# datalogger1_1.net
KiCad netlist of a schematic drawn in EAGLE
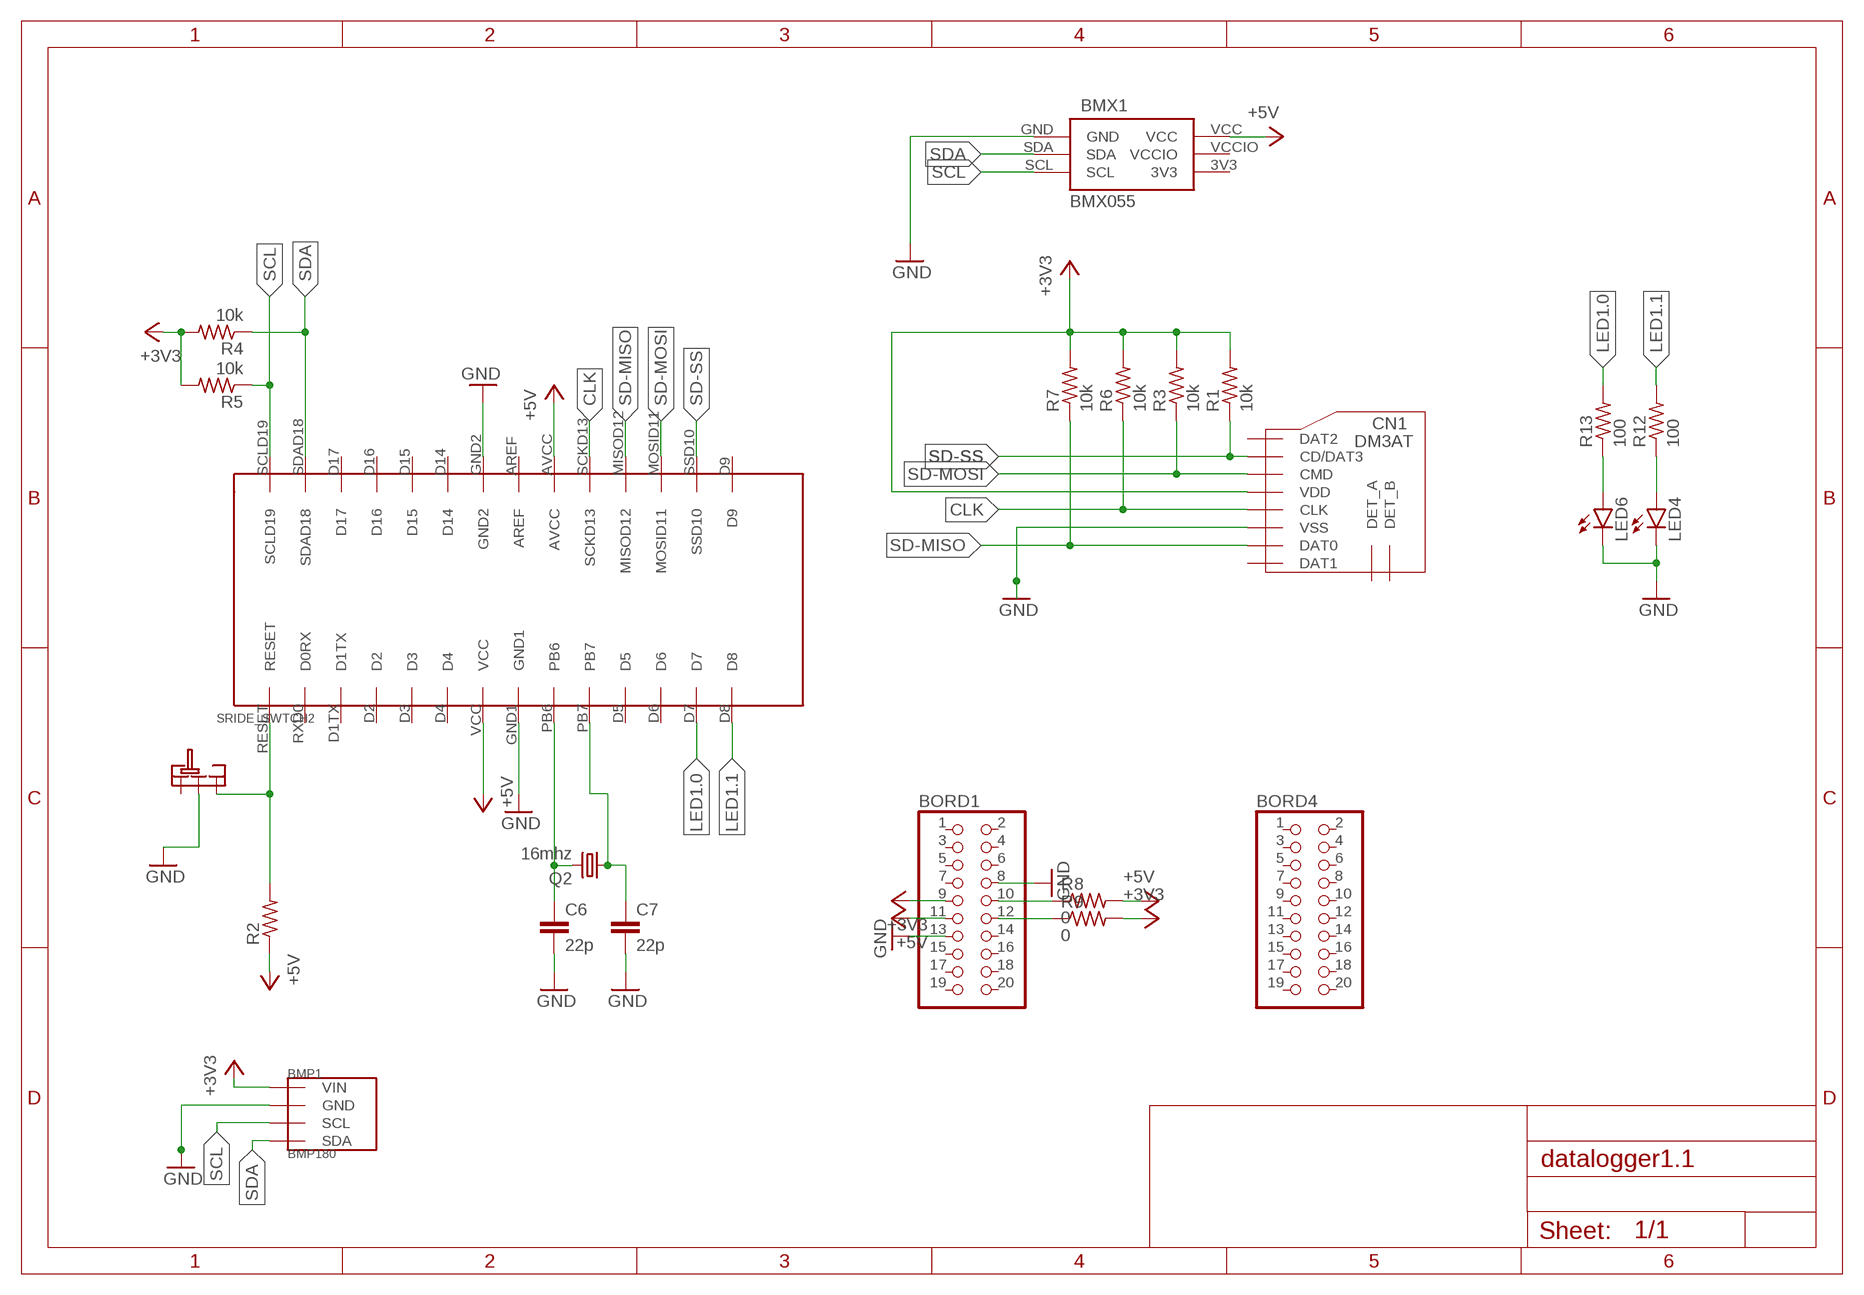
[diagram p0: schematic, sheet 1]

(export (version "E")
  (design (tool "Eeschema 10.0.6"))
  (components
    (comp (ref "BMP1")
      (value "BMP180")
      (footprint "eagle-import:GY-68")
      (libsource (lib "eagle-import") (part "BMP180"))
    )
    (comp (ref "BMX1")
      (value "BMX055")
      (footprint "eagle-import:BMX055")
      (libsource (lib "eagle-import") (part "BMX055"))
    )
    (comp (ref "BORD1")
      (value "PINHD-2X10/90")
      (footprint "eagle-import:2X10_90")
      (libsource (lib "eagle-import") (part "PINHD-2X10/90"))
    )
    (comp (ref "BORD4")
      (value "PINHD-2X10/90")
      (footprint "eagle-import:2X10_90")
      (libsource (lib "eagle-import") (part "PINHD-2X10/90"))
    )
    (comp (ref "C6")
      (value "22p")
      (footprint "eagle-import:C025-024X044")
      (libsource (lib "eagle-import") (part "C-EU025-024X044"))
    )
    (comp (ref "C7")
      (value "22p")
      (footprint "eagle-import:C025-024X044")
      (libsource (lib "eagle-import") (part "C-EU025-024X044"))
    )
    (comp (ref "CN1")
      (value "DM3AT")
      (footprint "eagle-import:DM3AT")
      (libsource (lib "eagle-import") (part "DM3AT"))
    )
    (comp (ref "LED4")
      (value "LED5MM")
      (footprint "eagle-import:LED5MM")
      (libsource (lib "eagle-import") (part "LED5MM"))
    )
    (comp (ref "LED6")
      (value "LED5MM")
      (footprint "eagle-import:LED5MM")
      (libsource (lib "eagle-import") (part "LED5MM"))
    )
    (comp (ref "Q2")
      (value "16mhz")
      (footprint "eagle-import:HC49_S")
      (libsource (lib "eagle-import") (part "CRYSTALHC49S"))
    )
    (comp (ref "R1")
      (value "10k")
      (footprint "eagle-import:0204_7")
      (libsource (lib "eagle-import") (part "R-US_0204/7"))
    )
    (comp (ref "R2")
      (value "R-US_0204/7")
      (footprint "eagle-import:0204_7")
      (libsource (lib "eagle-import") (part "R-US_0204/7"))
    )
    (comp (ref "R3")
      (value "10k")
      (footprint "eagle-import:0204_7")
      (libsource (lib "eagle-import") (part "R-US_0204/7"))
    )
    (comp (ref "R4")
      (value "10k")
      (footprint "eagle-import:0204_7")
      (libsource (lib "eagle-import") (part "R-US_0204/7"))
    )
    (comp (ref "R5")
      (value "10k")
      (footprint "eagle-import:0204_7")
      (libsource (lib "eagle-import") (part "R-US_0204/7"))
    )
    (comp (ref "R6")
      (value "10k")
      (footprint "eagle-import:0204_7")
      (libsource (lib "eagle-import") (part "R-US_0204/7"))
    )
    (comp (ref "R7")
      (value "10k")
      (footprint "eagle-import:0204_7")
      (libsource (lib "eagle-import") (part "R-US_0204/7"))
    )
    (comp (ref "R8")
      (value "0")
      (footprint "eagle-import:0204_7")
      (libsource (lib "eagle-import") (part "R-US_0204/7"))
    )
    (comp (ref "R9")
      (value "0")
      (footprint "eagle-import:0204_7")
      (libsource (lib "eagle-import") (part "R-US_0204/7"))
    )
    (comp (ref "R12")
      (value "100")
      (footprint "eagle-import:0204_7")
      (libsource (lib "eagle-import") (part "R-US_0204/7"))
    )
    (comp (ref "R13")
      (value "100")
      (footprint "eagle-import:0204_7")
      (libsource (lib "eagle-import") (part "R-US_0204/7"))
    )
    (comp (ref "SRIDE_SWTCH2")
      (value "SRIDE_SWITCH")
      (footprint "eagle-import:SRIDE_SWITCH")
      (libsource (lib "eagle-import") (part "SRIDE_SWITCH"))
    )
    (comp (ref "U$6")
      (value "ATMEGA238P")
      (footprint "eagle-import:ATMEGA328P")
      (libsource (lib "eagle-import") (part "ATMEGA238P"))
    )
  )
  (nets
    (net (code "1") (name "+3V3") (class "Default")
      (node (ref "BMP1") (pin "P1") (pinfunction "VIN_P1") (pintype "bidirectional"))
      (node (ref "BORD1") (pin "9") (pinfunction "9_9") (pintype "passive"))
      (node (ref "CN1") (pin "VDD") (pinfunction "VDD_VDD") (pintype "bidirectional"))
      (node (ref "R1") (pin "2") (pinfunction "2_2") (pintype "passive"))
      (node (ref "R3") (pin "2") (pinfunction "2_2") (pintype "passive"))
      (node (ref "R4") (pin "2") (pinfunction "2_2") (pintype "passive"))
      (node (ref "R5") (pin "2") (pinfunction "2_2") (pintype "passive"))
      (node (ref "R6") (pin "2") (pinfunction "2_2") (pintype "passive"))
      (node (ref "R7") (pin "2") (pinfunction "2_2") (pintype "passive"))
      (node (ref "R9") (pin "2") (pinfunction "2_2") (pintype "passive"))
    )
    (net (code "2") (name "+5V") (class "Default")
      (node (ref "BMX1") (pin "VCC") (pinfunction "VCC_VCC") (pintype "power_in"))
      (node (ref "BORD1") (pin "11") (pinfunction "11_11") (pintype "passive"))
      (node (ref "R2") (pin "1") (pinfunction "1_1") (pintype "passive"))
      (node (ref "R8") (pin "2") (pinfunction "2_2") (pintype "passive"))
      (node (ref "U$6") (pin "AVCC") (pinfunction "AVCC_AVCC") (pintype "bidirectional"))
      (node (ref "U$6") (pin "VCC") (pinfunction "VCC_VCC") (pintype "bidirectional"))
    )
    (net (code "3") (name "/3V3") (class "Default")
      (node (ref "BMX1") (pin "3V3") (pinfunction "3V3_3V3") (pintype "power_in"))
    )
    (net (code "4") (name "/VCCIO") (class "Default")
      (node (ref "BMX1") (pin "VCCIO") (pinfunction "VCCIO_VCCIO") (pintype "power_in"))
    )
    (net (code "5") (name "CLK") (class "Default")
      (node (ref "CN1") (pin "CLK") (pinfunction "CLK_CLK") (pintype "bidirectional"))
      (node (ref "R6") (pin "1") (pinfunction "1_1") (pintype "passive"))
      (node (ref "U$6") (pin "SCKD13") (pinfunction "SCKD13_SCKD13") (pintype "bidirectional"))
    )
    (net (code "6") (name "GND") (class "Default")
      (node (ref "BMP1") (pin "P2") (pinfunction "GND_P2") (pintype "bidirectional"))
      (node (ref "BMX1") (pin "GND") (pinfunction "GND_GND") (pintype "power_in"))
      (node (ref "BORD1") (pin "13") (pinfunction "13_13") (pintype "passive"))
      (node (ref "BORD1") (pin "8") (pinfunction "8_8") (pintype "passive"))
      (node (ref "C6") (pin "2") (pinfunction "2_2") (pintype "passive"))
      (node (ref "C7") (pin "2") (pinfunction "2_2") (pintype "passive"))
      (node (ref "CN1") (pin "VSS") (pinfunction "VSS_VSS") (pintype "bidirectional"))
      (node (ref "LED4") (pin "K") (pinfunction "C_K") (pintype "passive"))
      (node (ref "LED6") (pin "K") (pinfunction "C_K") (pintype "passive"))
      (node (ref "SRIDE_SWTCH2") (pin "LR") (pinfunction "LR_LR") (pintype "bidirectional"))
      (node (ref "U$6") (pin "GND1") (pinfunction "GND1_GND1") (pintype "bidirectional"))
      (node (ref "U$6") (pin "GND2") (pinfunction "GND2_GND2") (pintype "bidirectional"))
    )
    (net (code "7") (name "LED1.0") (class "Default")
      (node (ref "R13") (pin "2") (pinfunction "2_2") (pintype "passive"))
      (node (ref "U$6") (pin "D7") (pinfunction "D7_D7") (pintype "bidirectional"))
    )
    (net (code "8") (name "LED1.1") (class "Default")
      (node (ref "R12") (pin "2") (pinfunction "2_2") (pintype "passive"))
      (node (ref "U$6") (pin "D8") (pinfunction "D8_D8") (pintype "bidirectional"))
    )
    (net (code "9") (name "Net-(BORD1-Pad10)") (class "Default")
      (node (ref "BORD1") (pin "10") (pinfunction "10_10") (pintype "passive"))
      (node (ref "R8") (pin "1") (pinfunction "1_1") (pintype "passive"))
    )
    (net (code "10") (name "Net-(BORD1-Pad12)") (class "Default")
      (node (ref "BORD1") (pin "12") (pinfunction "12_12") (pintype "passive"))
      (node (ref "R9") (pin "1") (pinfunction "1_1") (pintype "passive"))
    )
    (net (code "11") (name "Net-(C6-Pad1)") (class "Default")
      (node (ref "C6") (pin "1") (pinfunction "1_1") (pintype "passive"))
      (node (ref "Q2") (pin "2") (pinfunction "2_2") (pintype "passive"))
      (node (ref "U$6") (pin "PB6") (pinfunction "PB6_PB6") (pintype "bidirectional"))
    )
    (net (code "12") (name "Net-(C7-Pad1)") (class "Default")
      (node (ref "C7") (pin "1") (pinfunction "1_1") (pintype "passive"))
      (node (ref "Q2") (pin "1") (pinfunction "1_1") (pintype "passive"))
      (node (ref "U$6") (pin "PB7") (pinfunction "PB7_PB7") (pintype "bidirectional"))
    )
    (net (code "13") (name "Net-(LED4-PadA)") (class "Default")
      (node (ref "LED4") (pin "A") (pinfunction "A_A") (pintype "passive"))
      (node (ref "R12") (pin "1") (pinfunction "1_1") (pintype "passive"))
    )
    (net (code "14") (name "Net-(LED6-PadA)") (class "Default")
      (node (ref "LED6") (pin "A") (pinfunction "A_A") (pintype "passive"))
      (node (ref "R13") (pin "1") (pinfunction "1_1") (pintype "passive"))
    )
    (net (code "15") (name "Net-(R2-Pad2)") (class "Default")
      (node (ref "R2") (pin "2") (pinfunction "2_2") (pintype "passive"))
      (node (ref "SRIDE_SWTCH2") (pin "R") (pinfunction "R_R") (pintype "bidirectional"))
      (node (ref "U$6") (pin "RESET") (pinfunction "RESET_RESET") (pintype "bidirectional"))
    )
    (net (code "16") (name "SCL") (class "Default")
      (node (ref "BMP1") (pin "P3") (pinfunction "SCL_P3") (pintype "bidirectional"))
      (node (ref "BMX1") (pin "SCL") (pinfunction "SCL_SCL") (pintype "bidirectional"))
      (node (ref "R5") (pin "1") (pinfunction "1_1") (pintype "passive"))
      (node (ref "U$6") (pin "SCLD19") (pinfunction "SCLD19_SCLD19") (pintype "bidirectional"))
    )
    (net (code "17") (name "SD-MISO") (class "Default")
      (node (ref "CN1") (pin "DAT0") (pinfunction "DAT0_DAT0") (pintype "bidirectional"))
      (node (ref "R7") (pin "1") (pinfunction "1_1") (pintype "passive"))
      (node (ref "U$6") (pin "MISOD12") (pinfunction "MISOD12_MISOD12") (pintype "bidirectional"))
    )
    (net (code "18") (name "SD-MOSI") (class "Default")
      (node (ref "CN1") (pin "CMD") (pinfunction "CMD_CMD") (pintype "bidirectional"))
      (node (ref "R3") (pin "1") (pinfunction "1_1") (pintype "passive"))
      (node (ref "U$6") (pin "MOSID11") (pinfunction "MOSID11_MOSID11") (pintype "bidirectional"))
    )
    (net (code "19") (name "SD-SS") (class "Default")
      (node (ref "CN1") (pin "CD/DAT3") (pinfunction "CD/DAT3_CD/DAT3") (pintype "bidirectional"))
      (node (ref "R1") (pin "1") (pinfunction "1_1") (pintype "passive"))
      (node (ref "U$6") (pin "SSD10") (pinfunction "SSD10_SSD10") (pintype "bidirectional"))
    )
    (net (code "20") (name "SDA") (class "Default")
      (node (ref "BMP1") (pin "P4") (pinfunction "SDA_P4") (pintype "bidirectional"))
      (node (ref "BMX1") (pin "SDA") (pinfunction "SDA_SDA") (pintype "bidirectional"))
      (node (ref "R4") (pin "1") (pinfunction "1_1") (pintype "passive"))
      (node (ref "U$6") (pin "SDAD18") (pinfunction "SDAD18_SDAD18") (pintype "bidirectional"))
    )
    (net (code "21") (name "unconnected-(BORD1-Pad1)") (class "Default")
      (node (ref "BORD1") (pin "1") (pinfunction "1_1") (pintype "passive"))
    )
    (net (code "22") (name "unconnected-(BORD1-Pad2)") (class "Default")
      (node (ref "BORD1") (pin "2") (pinfunction "2_2") (pintype "passive"))
    )
    (net (code "23") (name "unconnected-(BORD1-Pad3)") (class "Default")
      (node (ref "BORD1") (pin "3") (pinfunction "3_3") (pintype "passive"))
    )
    (net (code "24") (name "unconnected-(BORD1-Pad4)") (class "Default")
      (node (ref "BORD1") (pin "4") (pinfunction "4_4") (pintype "passive"))
    )
    (net (code "25") (name "unconnected-(BORD1-Pad5)") (class "Default")
      (node (ref "BORD1") (pin "5") (pinfunction "5_5") (pintype "passive"))
    )
    (net (code "26") (name "unconnected-(BORD1-Pad6)") (class "Default")
      (node (ref "BORD1") (pin "6") (pinfunction "6_6") (pintype "passive"))
    )
    (net (code "27") (name "unconnected-(BORD1-Pad7)") (class "Default")
      (node (ref "BORD1") (pin "7") (pinfunction "7_7") (pintype "passive"))
    )
    (net (code "28") (name "unconnected-(BORD1-Pad14)") (class "Default")
      (node (ref "BORD1") (pin "14") (pinfunction "14_14") (pintype "passive"))
    )
    (net (code "29") (name "unconnected-(BORD1-Pad15)") (class "Default")
      (node (ref "BORD1") (pin "15") (pinfunction "15_15") (pintype "passive"))
    )
    (net (code "30") (name "unconnected-(BORD1-Pad16)") (class "Default")
      (node (ref "BORD1") (pin "16") (pinfunction "16_16") (pintype "passive"))
    )
    (net (code "31") (name "unconnected-(BORD1-Pad17)") (class "Default")
      (node (ref "BORD1") (pin "17") (pinfunction "17_17") (pintype "passive"))
    )
    (net (code "32") (name "unconnected-(BORD1-Pad18)") (class "Default")
      (node (ref "BORD1") (pin "18") (pinfunction "18_18") (pintype "passive"))
    )
    (net (code "33") (name "unconnected-(BORD1-Pad19)") (class "Default")
      (node (ref "BORD1") (pin "19") (pinfunction "19_19") (pintype "passive"))
    )
    (net (code "34") (name "unconnected-(BORD1-Pad20)") (class "Default")
      (node (ref "BORD1") (pin "20") (pinfunction "20_20") (pintype "passive"))
    )
    (net (code "35") (name "unconnected-(BORD4-Pad1)") (class "Default")
      (node (ref "BORD4") (pin "1") (pinfunction "1_1") (pintype "passive"))
    )
    (net (code "36") (name "unconnected-(BORD4-Pad2)") (class "Default")
      (node (ref "BORD4") (pin "2") (pinfunction "2_2") (pintype "passive"))
    )
    (net (code "37") (name "unconnected-(BORD4-Pad3)") (class "Default")
      (node (ref "BORD4") (pin "3") (pinfunction "3_3") (pintype "passive"))
    )
    (net (code "38") (name "unconnected-(BORD4-Pad4)") (class "Default")
      (node (ref "BORD4") (pin "4") (pinfunction "4_4") (pintype "passive"))
    )
    (net (code "39") (name "unconnected-(BORD4-Pad5)") (class "Default")
      (node (ref "BORD4") (pin "5") (pinfunction "5_5") (pintype "passive"))
    )
    (net (code "40") (name "unconnected-(BORD4-Pad6)") (class "Default")
      (node (ref "BORD4") (pin "6") (pinfunction "6_6") (pintype "passive"))
    )
    (net (code "41") (name "unconnected-(BORD4-Pad7)") (class "Default")
      (node (ref "BORD4") (pin "7") (pinfunction "7_7") (pintype "passive"))
    )
    (net (code "42") (name "unconnected-(BORD4-Pad8)") (class "Default")
      (node (ref "BORD4") (pin "8") (pinfunction "8_8") (pintype "passive"))
    )
    (net (code "43") (name "unconnected-(BORD4-Pad9)") (class "Default")
      (node (ref "BORD4") (pin "9") (pinfunction "9_9") (pintype "passive"))
    )
    (net (code "44") (name "unconnected-(BORD4-Pad10)") (class "Default")
      (node (ref "BORD4") (pin "10") (pinfunction "10_10") (pintype "passive"))
    )
    (net (code "45") (name "unconnected-(BORD4-Pad11)") (class "Default")
      (node (ref "BORD4") (pin "11") (pinfunction "11_11") (pintype "passive"))
    )
    (net (code "46") (name "unconnected-(BORD4-Pad12)") (class "Default")
      (node (ref "BORD4") (pin "12") (pinfunction "12_12") (pintype "passive"))
    )
    (net (code "47") (name "unconnected-(BORD4-Pad13)") (class "Default")
      (node (ref "BORD4") (pin "13") (pinfunction "13_13") (pintype "passive"))
    )
    (net (code "48") (name "unconnected-(BORD4-Pad14)") (class "Default")
      (node (ref "BORD4") (pin "14") (pinfunction "14_14") (pintype "passive"))
    )
    (net (code "49") (name "unconnected-(BORD4-Pad15)") (class "Default")
      (node (ref "BORD4") (pin "15") (pinfunction "15_15") (pintype "passive"))
    )
    (net (code "50") (name "unconnected-(BORD4-Pad16)") (class "Default")
      (node (ref "BORD4") (pin "16") (pinfunction "16_16") (pintype "passive"))
    )
    (net (code "51") (name "unconnected-(BORD4-Pad17)") (class "Default")
      (node (ref "BORD4") (pin "17") (pinfunction "17_17") (pintype "passive"))
    )
    (net (code "52") (name "unconnected-(BORD4-Pad18)") (class "Default")
      (node (ref "BORD4") (pin "18") (pinfunction "18_18") (pintype "passive"))
    )
    (net (code "53") (name "unconnected-(BORD4-Pad19)") (class "Default")
      (node (ref "BORD4") (pin "19") (pinfunction "19_19") (pintype "passive"))
    )
    (net (code "54") (name "unconnected-(BORD4-Pad20)") (class "Default")
      (node (ref "BORD4") (pin "20") (pinfunction "20_20") (pintype "passive"))
    )
    (net (code "55") (name "unconnected-(CN1-PadDAT1)") (class "Default")
      (node (ref "CN1") (pin "DAT1") (pinfunction "DAT1_DAT1") (pintype "bidirectional"))
    )
    (net (code "56") (name "unconnected-(CN1-PadDAT2)") (class "Default")
      (node (ref "CN1") (pin "DAT2") (pinfunction "DAT2_DAT2") (pintype "bidirectional"))
    )
    (net (code "57") (name "unconnected-(CN1-PadDET_A)") (class "Default")
      (node (ref "CN1") (pin "DET_A") (pinfunction "DET_A_DET_A") (pintype "bidirectional"))
    )
    (net (code "58") (name "unconnected-(CN1-PadDET_B)") (class "Default")
      (node (ref "CN1") (pin "DET_B") (pinfunction "DET_B_DET_B") (pintype "bidirectional"))
    )
    (net (code "59") (name "unconnected-(SRIDE_SWTCH2-PadL)") (class "Default")
      (node (ref "SRIDE_SWTCH2") (pin "L") (pinfunction "L_L") (pintype "bidirectional"))
    )
    (net (code "60") (name "unconnected-(U$6-D0RX-PadRXD0)") (class "Default")
      (node (ref "U$6") (pin "RXD0") (pinfunction "D0RX_RXD0") (pintype "bidirectional"))
    )
    (net (code "61") (name "unconnected-(U$6-PadAREF)") (class "Default")
      (node (ref "U$6") (pin "AREF") (pinfunction "AREF_AREF") (pintype "bidirectional"))
    )
    (net (code "62") (name "unconnected-(U$6-PadD1TX)") (class "Default")
      (node (ref "U$6") (pin "D1TX") (pinfunction "D1TX_D1TX") (pintype "bidirectional"))
    )
    (net (code "63") (name "unconnected-(U$6-PadD2)") (class "Default")
      (node (ref "U$6") (pin "D2") (pinfunction "D2_D2") (pintype "bidirectional"))
    )
    (net (code "64") (name "unconnected-(U$6-PadD3)") (class "Default")
      (node (ref "U$6") (pin "D3") (pinfunction "D3_D3") (pintype "bidirectional"))
    )
    (net (code "65") (name "unconnected-(U$6-PadD4)") (class "Default")
      (node (ref "U$6") (pin "D4") (pinfunction "D4_D4") (pintype "bidirectional"))
    )
    (net (code "66") (name "unconnected-(U$6-PadD5)") (class "Default")
      (node (ref "U$6") (pin "D5") (pinfunction "D5_D5") (pintype "bidirectional"))
    )
    (net (code "67") (name "unconnected-(U$6-PadD6)") (class "Default")
      (node (ref "U$6") (pin "D6") (pinfunction "D6_D6") (pintype "bidirectional"))
    )
    (net (code "68") (name "unconnected-(U$6-PadD9)") (class "Default")
      (node (ref "U$6") (pin "D9") (pinfunction "D9_D9") (pintype "bidirectional"))
    )
    (net (code "69") (name "unconnected-(U$6-PadD14)") (class "Default")
      (node (ref "U$6") (pin "D14") (pinfunction "D14_D14") (pintype "bidirectional"))
    )
    (net (code "70") (name "unconnected-(U$6-PadD15)") (class "Default")
      (node (ref "U$6") (pin "D15") (pinfunction "D15_D15") (pintype "bidirectional"))
    )
    (net (code "71") (name "unconnected-(U$6-PadD16)") (class "Default")
      (node (ref "U$6") (pin "D16") (pinfunction "D16_D16") (pintype "bidirectional"))
    )
    (net (code "72") (name "unconnected-(U$6-PadD17)") (class "Default")
      (node (ref "U$6") (pin "D17") (pinfunction "D17_D17") (pintype "bidirectional"))
    )
  )
)
